# LightSensorCircuitNoAmp.net
KiCad netlist of a schematic drawn in EAGLE
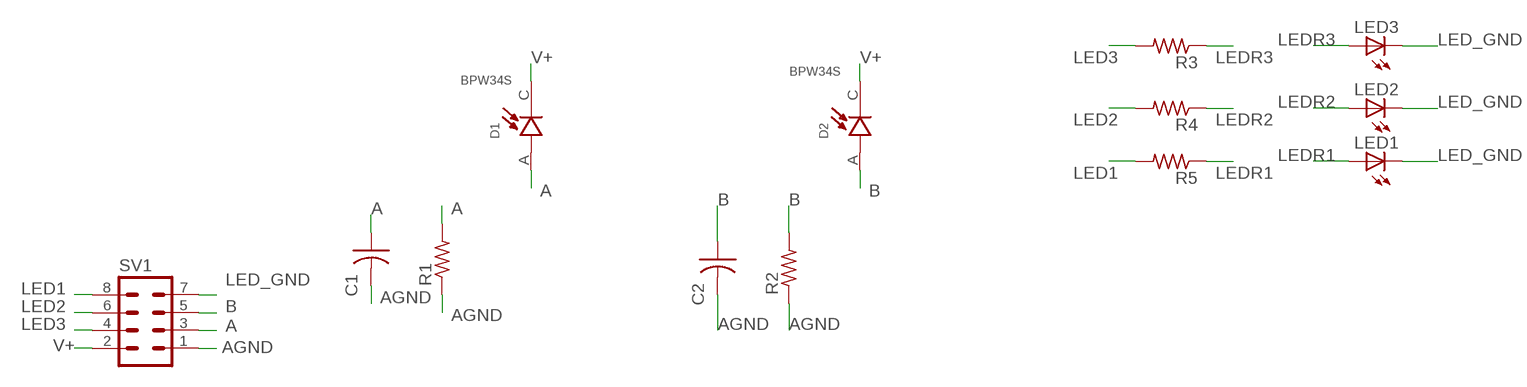
[diagram p0: schematic, sheet 1]

(export (version "E")
  (design (tool "Eeschema 10.0.6"))
  (components
    (comp (ref "C1")
      (value "C-US025-025X050")
      (footprint "eagle-import:C025-025X050")
      (libsource (lib "eagle-import") (part "C-US025-025X050"))
    )
    (comp (ref "C2")
      (value "C-US025-025X050")
      (footprint "eagle-import:C025-025X050")
      (libsource (lib "eagle-import") (part "C-US025-025X050"))
    )
    (comp (ref "D1")
      (value "BPW34S")
      (footprint "eagle-import:DIO_BPW34S")
      (fields (field (name "MF") "Vishay Semiconductor Opto Division"))
      (libsource (lib "eagle-import") (part "BPW34S"))
    )
    (comp (ref "D2")
      (value "BPW34S")
      (footprint "eagle-import:DIO_BPW34S")
      (fields (field (name "MF") "Vishay Semiconductor Opto Division"))
      (libsource (lib "eagle-import") (part "BPW34S"))
    )
    (comp (ref "LED1")
      (value "LEDCHIPLED_1206")
      (footprint "eagle-import:CHIPLED_1206")
      (libsource (lib "eagle-import") (part "LEDCHIPLED_1206"))
    )
    (comp (ref "LED2")
      (value "LEDCHIPLED_1206")
      (footprint "eagle-import:CHIPLED_1206")
      (libsource (lib "eagle-import") (part "LEDCHIPLED_1206"))
    )
    (comp (ref "LED3")
      (value "LEDCHIPLED_1206")
      (footprint "eagle-import:CHIPLED_1206")
      (libsource (lib "eagle-import") (part "LEDCHIPLED_1206"))
    )
    (comp (ref "R1")
      (value "R-US_0204/5")
      (footprint "eagle-import:0204_5")
      (libsource (lib "eagle-import") (part "R-US_0204/5"))
    )
    (comp (ref "R2")
      (value "R-US_0204/5")
      (footprint "eagle-import:0204_5")
      (libsource (lib "eagle-import") (part "R-US_0204/5"))
    )
    (comp (ref "R3")
      (value "R-US_0204/5")
      (footprint "eagle-import:0204_5")
      (libsource (lib "eagle-import") (part "R-US_0204/5"))
    )
    (comp (ref "R4")
      (value "R-US_0204/5")
      (footprint "eagle-import:0204_5")
      (libsource (lib "eagle-import") (part "R-US_0204/5"))
    )
    (comp (ref "R5")
      (value "R-US_0204/5")
      (footprint "eagle-import:0204_5")
      (libsource (lib "eagle-import") (part "R-US_0204/5"))
    )
    (comp (ref "SV1")
      (value "MA04-2")
      (footprint "eagle-import:MA04-2")
      (libsource (lib "eagle-import") (part "MA04-2"))
    )
  )
  (nets
    (net (code "1") (name "/A") (class "Default")
      (node (ref "C1") (pin "1") (pinfunction "1_1") (pintype "passive"))
      (node (ref "D1") (pin "A") (pinfunction "A_A") (pintype "passive"))
      (node (ref "R1") (pin "2") (pinfunction "2_2") (pintype "passive"))
      (node (ref "SV1") (pin "3") (pinfunction "3_3") (pintype "passive"))
    )
    (net (code "2") (name "/AGND") (class "Default")
      (node (ref "C1") (pin "2") (pinfunction "2_2") (pintype "passive"))
      (node (ref "C2") (pin "2") (pinfunction "2_2") (pintype "passive"))
      (node (ref "R1") (pin "1") (pinfunction "1_1") (pintype "passive"))
      (node (ref "R2") (pin "1") (pinfunction "1_1") (pintype "passive"))
      (node (ref "SV1") (pin "1") (pinfunction "1_1") (pintype "passive"))
    )
    (net (code "3") (name "/B") (class "Default")
      (node (ref "C2") (pin "1") (pinfunction "1_1") (pintype "passive"))
      (node (ref "D2") (pin "A") (pinfunction "A_A") (pintype "passive"))
      (node (ref "R2") (pin "2") (pinfunction "2_2") (pintype "passive"))
      (node (ref "SV1") (pin "5") (pinfunction "5_5") (pintype "passive"))
    )
    (net (code "4") (name "/LED1") (class "Default")
      (node (ref "R5") (pin "2") (pinfunction "2_2") (pintype "passive"))
      (node (ref "SV1") (pin "8") (pinfunction "8_8") (pintype "passive"))
    )
    (net (code "5") (name "/LED2") (class "Default")
      (node (ref "R4") (pin "2") (pinfunction "2_2") (pintype "passive"))
      (node (ref "SV1") (pin "6") (pinfunction "6_6") (pintype "passive"))
    )
    (net (code "6") (name "/LED3") (class "Default")
      (node (ref "R3") (pin "2") (pinfunction "2_2") (pintype "passive"))
      (node (ref "SV1") (pin "4") (pinfunction "4_4") (pintype "passive"))
    )
    (net (code "7") (name "/LEDR1") (class "Default")
      (node (ref "LED1") (pin "A") (pinfunction "A_A") (pintype "passive"))
      (node (ref "R5") (pin "1") (pinfunction "1_1") (pintype "passive"))
    )
    (net (code "8") (name "/LEDR2") (class "Default")
      (node (ref "LED2") (pin "A") (pinfunction "A_A") (pintype "passive"))
      (node (ref "R4") (pin "1") (pinfunction "1_1") (pintype "passive"))
    )
    (net (code "9") (name "/LEDR3") (class "Default")
      (node (ref "LED3") (pin "A") (pinfunction "A_A") (pintype "passive"))
      (node (ref "R3") (pin "1") (pinfunction "1_1") (pintype "passive"))
    )
    (net (code "10") (name "/LED_GND") (class "Default")
      (node (ref "LED1") (pin "C") (pinfunction "C_C") (pintype "passive"))
      (node (ref "LED2") (pin "C") (pinfunction "C_C") (pintype "passive"))
      (node (ref "LED3") (pin "C") (pinfunction "C_C") (pintype "passive"))
      (node (ref "SV1") (pin "7") (pinfunction "7_7") (pintype "passive"))
    )
    (net (code "11") (name "/V+") (class "Default")
      (node (ref "D1") (pin "C") (pinfunction "C_C") (pintype "passive"))
      (node (ref "D2") (pin "C") (pinfunction "C_C") (pintype "passive"))
      (node (ref "SV1") (pin "2") (pinfunction "2_2") (pintype "passive"))
    )
  )
)
